# schematic.net
KiCad netlist of a schematic drawn in EAGLE
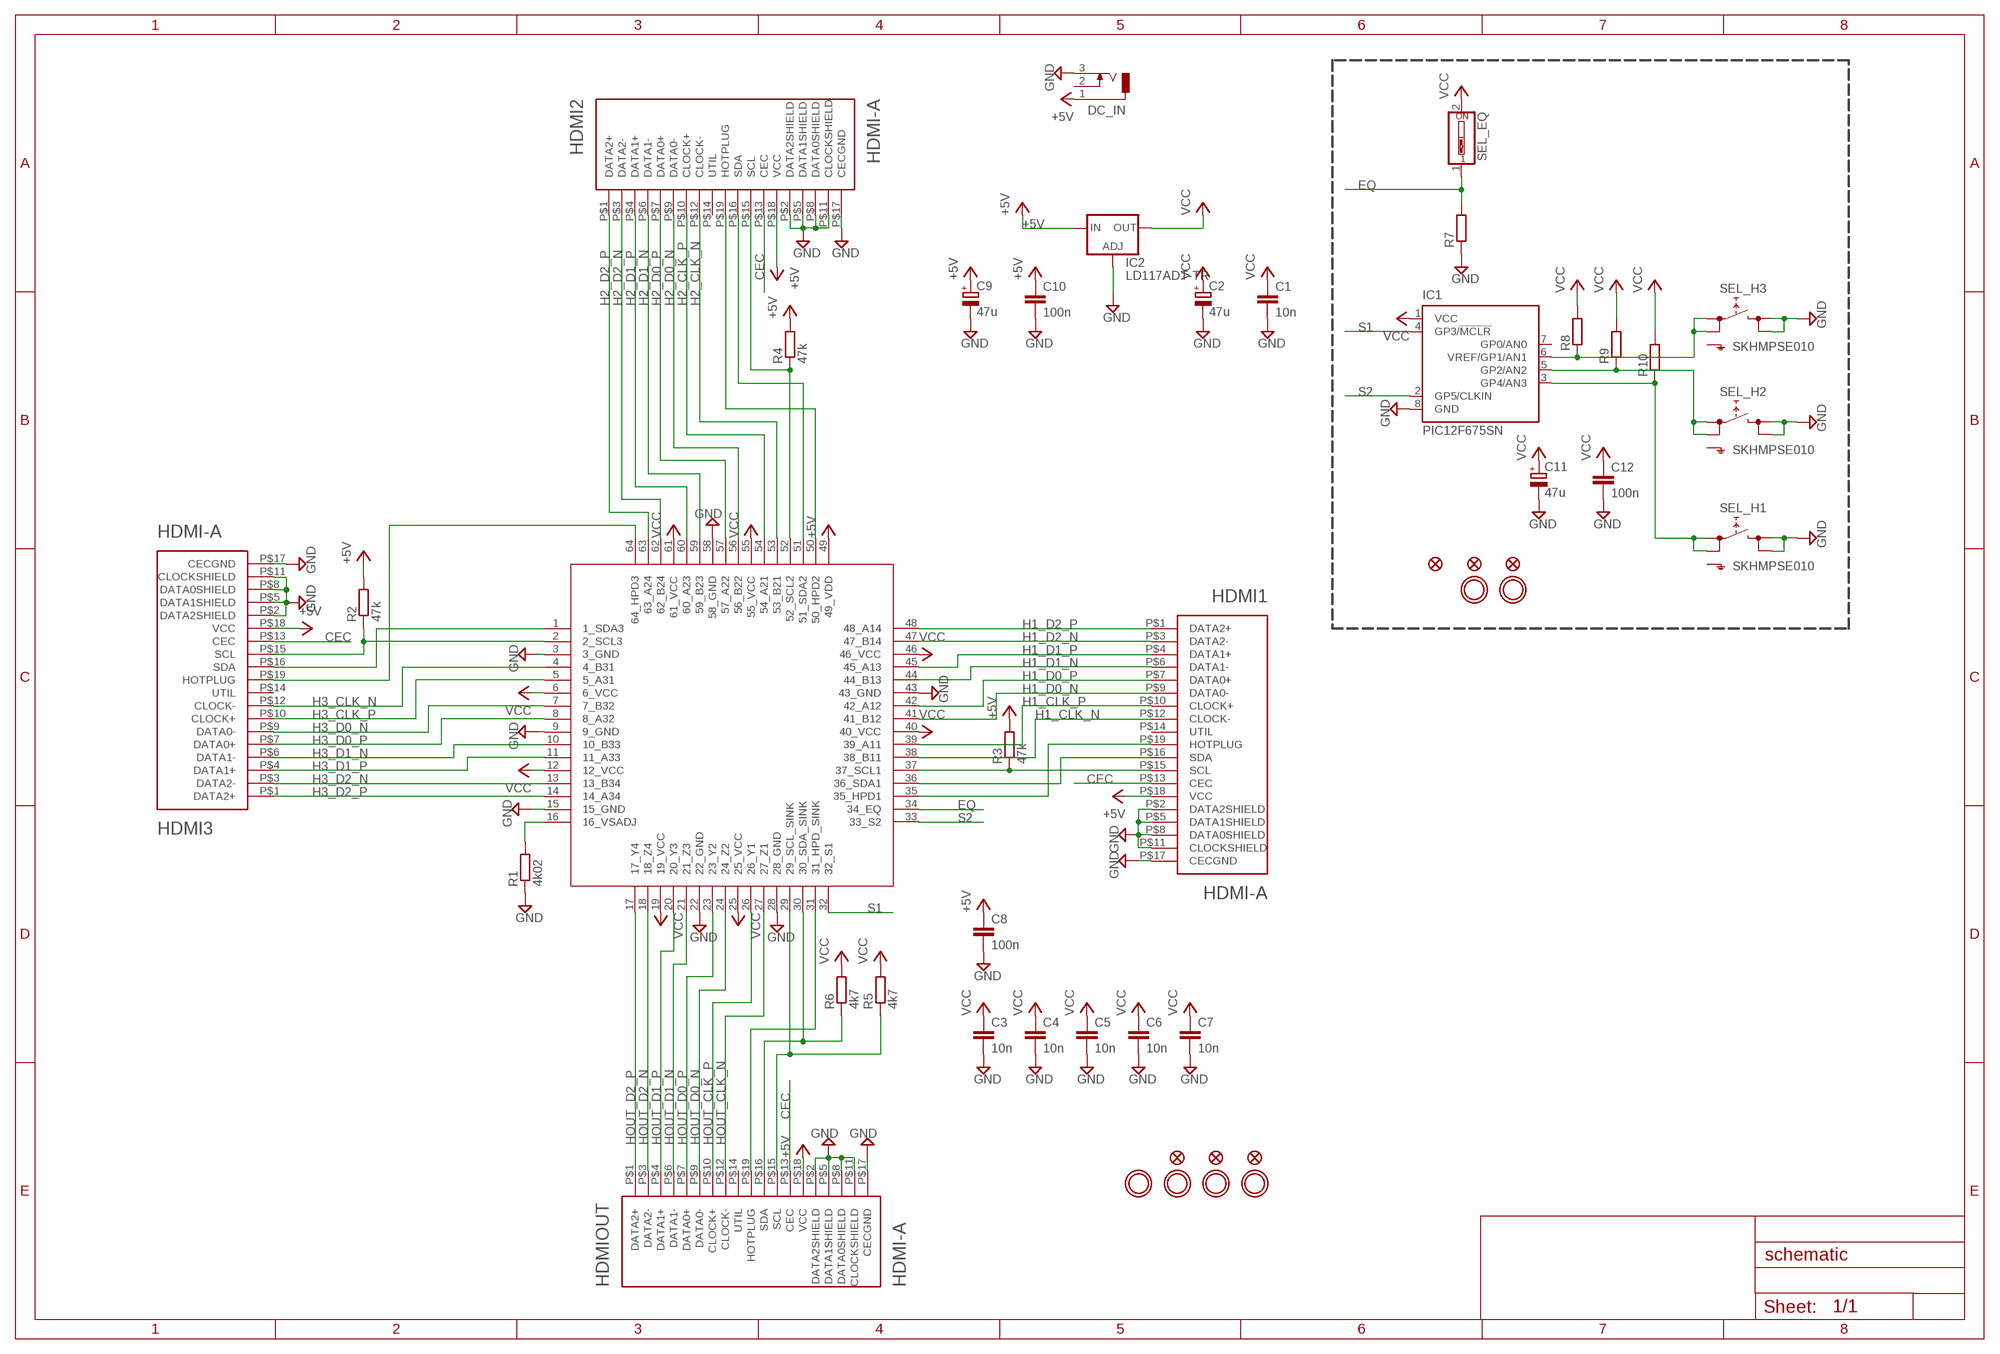
[diagram p0: schematic, sheet 1]

(export (version "E")
  (design (tool "Eeschema 10.0.6"))
  (components
    (comp (ref "C1")
      (value "10n")
      (footprint "eagle-import:C0402")
      (libsource (lib "eagle-import") (part "C-EUC0402"))
    )
    (comp (ref "C2")
      (value "47u")
      (footprint "eagle-import:SMC_A")
      (libsource (lib "eagle-import") (part "CPOL-EUSMCA"))
    )
    (comp (ref "C3")
      (value "10n")
      (footprint "eagle-import:0402")
      (libsource (lib "eagle-import") (part "C0402"))
    )
    (comp (ref "C4")
      (value "10n")
      (footprint "eagle-import:0402")
      (libsource (lib "eagle-import") (part "C0402"))
    )
    (comp (ref "C5")
      (value "10n")
      (footprint "eagle-import:0402")
      (libsource (lib "eagle-import") (part "C0402"))
    )
    (comp (ref "C6")
      (value "10n")
      (footprint "eagle-import:0402")
      (libsource (lib "eagle-import") (part "C0402"))
    )
    (comp (ref "C7")
      (value "10n")
      (footprint "eagle-import:0402")
      (libsource (lib "eagle-import") (part "C0402"))
    )
    (comp (ref "C8")
      (value "100n")
      (footprint "eagle-import:0402")
      (libsource (lib "eagle-import") (part "C0402"))
    )
    (comp (ref "C9")
      (value "47u")
      (footprint "eagle-import:SMC_A")
      (libsource (lib "eagle-import") (part "CPOL-EUSMCA"))
    )
    (comp (ref "C10")
      (value "100n")
      (footprint "eagle-import:C0402")
      (libsource (lib "eagle-import") (part "C-EUC0402"))
    )
    (comp (ref "C11")
      (value "47u")
      (footprint "eagle-import:SMC_A")
      (libsource (lib "eagle-import") (part "CPOL-EUSMCA"))
    )
    (comp (ref "C12")
      (value "100n")
      (footprint "eagle-import:C0402")
      (libsource (lib "eagle-import") (part "C-EUC0402"))
    )
    (comp (ref "DC_IN")
      (value "DCJ0303")
      (footprint "eagle-import:DCJ0303")
      (libsource (lib "eagle-import") (part "DCJ0303"))
    )
    (comp (ref "FID1")
      (value "FIDUCIAL\"\"")
      (footprint "eagle-import:FIDUCIAL_1MM")
      (libsource (lib "eagle-import") (part "FIDUCIAL{dblquote}{dblquote}"))
    )
    (comp (ref "FID2")
      (value "FIDUCIAL\"\"")
      (footprint "eagle-import:FIDUCIAL_1MM")
      (libsource (lib "eagle-import") (part "FIDUCIAL{dblquote}{dblquote}"))
    )
    (comp (ref "FID3")
      (value "FIDUCIAL\"\"")
      (footprint "eagle-import:FIDUCIAL_1MM")
      (libsource (lib "eagle-import") (part "FIDUCIAL{dblquote}{dblquote}"))
    )
    (comp (ref "FID4")
      (value "FIDUCIAL\"\"")
      (footprint "eagle-import:FIDUCIAL_1MM")
      (libsource (lib "eagle-import") (part "FIDUCIAL{dblquote}{dblquote}"))
    )
    (comp (ref "FID5")
      (value "FIDUCIAL\"\"")
      (footprint "eagle-import:FIDUCIAL_1MM")
      (libsource (lib "eagle-import") (part "FIDUCIAL{dblquote}{dblquote}"))
    )
    (comp (ref "FID6")
      (value "FIDUCIAL\"\"")
      (footprint "eagle-import:FIDUCIAL_1MM")
      (libsource (lib "eagle-import") (part "FIDUCIAL{dblquote}{dblquote}"))
    )
    (comp (ref "HDMI1")
      (value "HDMI-A")
      (footprint "eagle-import:HDMI_A")
      (libsource (lib "eagle-import") (part "HDMI-A"))
    )
    (comp (ref "HDMI2")
      (value "HDMI-A")
      (footprint "eagle-import:HDMI_A")
      (libsource (lib "eagle-import") (part "HDMI-A"))
    )
    (comp (ref "HDMI3")
      (value "HDMI-A")
      (footprint "eagle-import:HDMI_A")
      (libsource (lib "eagle-import") (part "HDMI-A"))
    )
    (comp (ref "HDMIOUT")
      (value "HDMI-A")
      (footprint "eagle-import:HDMI_A")
      (libsource (lib "eagle-import") (part "HDMI-A"))
    )
    (comp (ref "IC1")
      (value "PIC12F675SN")
      (footprint "eagle-import:SO-08")
      (fields (field (name "MF") "MICROCHIP") (field (name "MPN") "PIC12F675-E/SN"))
      (libsource (lib "eagle-import") (part "PIC12F675SN"))
    )
    (comp (ref "IC2")
      (value "LD117ADT-TR")
      (footprint "eagle-import:DPACK")
      (libsource (lib "eagle-import") (part "LD117A?DT-TR"))
    )
    (comp (ref "R1")
      (value "4k02")
      (footprint "eagle-import:0402")
      (libsource (lib "eagle-import") (part "R0402"))
    )
    (comp (ref "R2")
      (value "47k")
      (footprint "eagle-import:0402")
      (libsource (lib "eagle-import") (part "R0402"))
    )
    (comp (ref "R3")
      (value "47k")
      (footprint "eagle-import:0402")
      (libsource (lib "eagle-import") (part "R0402"))
    )
    (comp (ref "R4")
      (value "47k")
      (footprint "eagle-import:0402")
      (libsource (lib "eagle-import") (part "R0402"))
    )
    (comp (ref "R5")
      (value "4k7")
      (footprint "eagle-import:0402")
      (libsource (lib "eagle-import") (part "R0402"))
    )
    (comp (ref "R6")
      (value "4k7")
      (footprint "eagle-import:0402")
      (libsource (lib "eagle-import") (part "R0402"))
    )
    (comp (ref "R7")
      (value "R-EU_R0805")
      (footprint "eagle-import:R0805")
      (libsource (lib "eagle-import") (part "R-EU_R0805"))
    )
    (comp (ref "R8")
      (value "R-EU_R0805")
      (footprint "eagle-import:R0805")
      (libsource (lib "eagle-import") (part "R-EU_R0805"))
    )
    (comp (ref "R9")
      (value "R-EU_R0805")
      (footprint "eagle-import:R0805")
      (libsource (lib "eagle-import") (part "R-EU_R0805"))
    )
    (comp (ref "R10")
      (value "R-EU_R0805")
      (footprint "eagle-import:R0805")
      (libsource (lib "eagle-import") (part "R-EU_R0805"))
    )
    (comp (ref "SEL_EQ")
      (value "SW_DIP-1")
      (footprint "eagle-import:EDG-01")
      (libsource (lib "eagle-import") (part "SW_DIP-1"))
    )
    (comp (ref "SEL_H1")
      (value "SKHMPSE010")
      (footprint "eagle-import:SKHMPXE010")
      (libsource (lib "eagle-import") (part "SKHMPE010S"))
    )
    (comp (ref "SEL_H2")
      (value "SKHMPSE010")
      (footprint "eagle-import:SKHMPXE010")
      (libsource (lib "eagle-import") (part "SKHMPE010S"))
    )
    (comp (ref "SEL_H3")
      (value "SKHMPSE010")
      (footprint "eagle-import:SKHMPXE010")
      (libsource (lib "eagle-import") (part "SKHMPE010S"))
    )
    (comp (ref "U$1")
      (value "MOUNTINGHOLE3.0")
      (footprint "eagle-import:MOUNTINGHOLE_3.0_PLATED")
      (libsource (lib "eagle-import") (part "MOUNTINGHOLE3.0"))
    )
    (comp (ref "U$2")
      (value "MOUNTINGHOLE3.0")
      (footprint "eagle-import:MOUNTINGHOLE_3.0_PLATED")
      (libsource (lib "eagle-import") (part "MOUNTINGHOLE3.0"))
    )
    (comp (ref "U$31")
      (value "MOUNTINGHOLE3.0")
      (footprint "eagle-import:MOUNTINGHOLE_3.0_PLATED")
      (libsource (lib "eagle-import") (part "MOUNTINGHOLE3.0"))
    )
    (comp (ref "U$32")
      (value "MOUNTINGHOLE3.0")
      (footprint "eagle-import:MOUNTINGHOLE_3.0_PLATED")
      (libsource (lib "eagle-import") (part "MOUNTINGHOLE3.0"))
    )
    (comp (ref "U$33")
      (value "MOUNTINGHOLE3.0")
      (footprint "eagle-import:MOUNTINGHOLE_3.0_PLATED")
      (libsource (lib "eagle-import") (part "MOUNTINGHOLE3.0"))
    )
    (comp (ref "U$34")
      (value "MOUNTINGHOLE3.0")
      (footprint "eagle-import:MOUNTINGHOLE_3.0_PLATED")
      (libsource (lib "eagle-import") (part "MOUNTINGHOLE3.0"))
    )
    (comp (ref "U1")
      (value "TMDS351TQFP64")
      (footprint "eagle-import:QFP50P1200X1200X120-64")
      (libsource (lib "eagle-import") (part "TMDS351TQFP64"))
    )
  )
  (nets
    (net (code "1") (name "+5V") (class "Default")
      (node (ref "C10") (pin "1") (pinfunction "1_1") (pintype "passive"))
      (node (ref "C8") (pin "1") (pinfunction "1_1") (pintype "passive"))
      (node (ref "C9") (pin "+") (pinfunction "+_+") (pintype "passive"))
      (node (ref "DC_IN") (pin "1") (pinfunction "1_1") (pintype "passive"))
      (node (ref "HDMI1") (pin "P$18") (pinfunction "VCC_P$18") (pintype "bidirectional"))
      (node (ref "HDMI2") (pin "P$18") (pinfunction "VCC_P$18") (pintype "bidirectional"))
      (node (ref "HDMI3") (pin "P$18") (pinfunction "VCC_P$18") (pintype "bidirectional"))
      (node (ref "HDMIOUT") (pin "P$18") (pinfunction "VCC_P$18") (pintype "bidirectional"))
      (node (ref "IC2") (pin "3") (pinfunction "IN_3") (pintype "input"))
      (node (ref "R2") (pin "2") (pinfunction "2_2") (pintype "passive"))
      (node (ref "R3") (pin "2") (pinfunction "2_2") (pintype "passive"))
      (node (ref "R4") (pin "2") (pinfunction "2_2") (pintype "passive"))
      (node (ref "U1") (pin "49") (pinfunction "49_VDD_49") (pintype "bidirectional"))
    )
    (net (code "2") (name "/CEC") (class "Default")
      (node (ref "HDMI1") (pin "P$13") (pinfunction "CEC_P$13") (pintype "bidirectional"))
      (node (ref "HDMI2") (pin "P$13") (pinfunction "CEC_P$13") (pintype "bidirectional"))
      (node (ref "HDMI3") (pin "P$13") (pinfunction "CEC_P$13") (pintype "bidirectional"))
      (node (ref "HDMIOUT") (pin "P$13") (pinfunction "CEC_P$13") (pintype "bidirectional"))
    )
    (net (code "3") (name "/EQ") (class "Default")
      (node (ref "R7") (pin "2") (pinfunction "2_2") (pintype "passive"))
      (node (ref "SEL_EQ") (pin "1") (pinfunction "1_1") (pintype "passive"))
      (node (ref "U1") (pin "34") (pinfunction "34_EQ_34") (pintype "bidirectional"))
    )
    (net (code "4") (name "/H1_CLK_N") (class "Default")
      (node (ref "HDMI1") (pin "P$12") (pinfunction "CLOCK-_P$12") (pintype "bidirectional"))
      (node (ref "U1") (pin "38") (pinfunction "38_B11_38") (pintype "bidirectional"))
    )
    (net (code "5") (name "/H1_CLK_P") (class "Default")
      (node (ref "HDMI1") (pin "P$10") (pinfunction "CLOCK+_P$10") (pintype "bidirectional"))
      (node (ref "U1") (pin "39") (pinfunction "39_A11_39") (pintype "bidirectional"))
    )
    (net (code "6") (name "/H1_D0_N") (class "Default")
      (node (ref "HDMI1") (pin "P$9") (pinfunction "DATA0-_P$9") (pintype "bidirectional"))
      (node (ref "U1") (pin "41") (pinfunction "41_B12_41") (pintype "bidirectional"))
    )
    (net (code "7") (name "/H1_D0_P") (class "Default")
      (node (ref "HDMI1") (pin "P$7") (pinfunction "DATA0+_P$7") (pintype "bidirectional"))
      (node (ref "U1") (pin "42") (pinfunction "42_A12_42") (pintype "bidirectional"))
    )
    (net (code "8") (name "/H1_D1_N") (class "Default")
      (node (ref "HDMI1") (pin "P$6") (pinfunction "DATA1-_P$6") (pintype "bidirectional"))
      (node (ref "U1") (pin "44") (pinfunction "44_B13_44") (pintype "bidirectional"))
    )
    (net (code "9") (name "/H1_D1_P") (class "Default")
      (node (ref "HDMI1") (pin "P$4") (pinfunction "DATA1+_P$4") (pintype "bidirectional"))
      (node (ref "U1") (pin "45") (pinfunction "45_A13_45") (pintype "bidirectional"))
    )
    (net (code "10") (name "/H1_D2_N") (class "Default")
      (node (ref "HDMI1") (pin "P$3") (pinfunction "DATA2-_P$3") (pintype "bidirectional"))
      (node (ref "U1") (pin "47") (pinfunction "47_B14_47") (pintype "bidirectional"))
    )
    (net (code "11") (name "/H1_D2_P") (class "Default")
      (node (ref "HDMI1") (pin "P$1") (pinfunction "DATA2+_P$1") (pintype "bidirectional"))
      (node (ref "U1") (pin "48") (pinfunction "48_A14_48") (pintype "bidirectional"))
    )
    (net (code "12") (name "/H2_CLK_N") (class "Default")
      (node (ref "HDMI2") (pin "P$12") (pinfunction "CLOCK-_P$12") (pintype "bidirectional"))
      (node (ref "U1") (pin "53") (pinfunction "53_B21_53") (pintype "bidirectional"))
    )
    (net (code "13") (name "/H2_CLK_P") (class "Default")
      (node (ref "HDMI2") (pin "P$10") (pinfunction "CLOCK+_P$10") (pintype "bidirectional"))
      (node (ref "U1") (pin "54") (pinfunction "54_A21_54") (pintype "bidirectional"))
    )
    (net (code "14") (name "/H2_D0_N") (class "Default")
      (node (ref "HDMI2") (pin "P$9") (pinfunction "DATA0-_P$9") (pintype "bidirectional"))
      (node (ref "U1") (pin "56") (pinfunction "56_B22_56") (pintype "bidirectional"))
    )
    (net (code "15") (name "/H2_D0_P") (class "Default")
      (node (ref "HDMI2") (pin "P$7") (pinfunction "DATA0+_P$7") (pintype "bidirectional"))
      (node (ref "U1") (pin "57") (pinfunction "57_A22_57") (pintype "bidirectional"))
    )
    (net (code "16") (name "/H2_D1_N") (class "Default")
      (node (ref "HDMI2") (pin "P$6") (pinfunction "DATA1-_P$6") (pintype "bidirectional"))
      (node (ref "U1") (pin "59") (pinfunction "59_B23_59") (pintype "bidirectional"))
    )
    (net (code "17") (name "/H2_D1_P") (class "Default")
      (node (ref "HDMI2") (pin "P$4") (pinfunction "DATA1+_P$4") (pintype "bidirectional"))
      (node (ref "U1") (pin "60") (pinfunction "60_A23_60") (pintype "bidirectional"))
    )
    (net (code "18") (name "/H2_D2_N") (class "Default")
      (node (ref "HDMI2") (pin "P$3") (pinfunction "DATA2-_P$3") (pintype "bidirectional"))
      (node (ref "U1") (pin "62") (pinfunction "62_B24_62") (pintype "bidirectional"))
    )
    (net (code "19") (name "/H2_D2_P") (class "Default")
      (node (ref "HDMI2") (pin "P$1") (pinfunction "DATA2+_P$1") (pintype "bidirectional"))
      (node (ref "U1") (pin "63") (pinfunction "63_A24_63") (pintype "bidirectional"))
    )
    (net (code "20") (name "/H3_CLK_N") (class "Default")
      (node (ref "HDMI3") (pin "P$12") (pinfunction "CLOCK-_P$12") (pintype "bidirectional"))
      (node (ref "U1") (pin "4") (pinfunction "4_B31_4") (pintype "bidirectional"))
    )
    (net (code "21") (name "/H3_CLK_P") (class "Default")
      (node (ref "HDMI3") (pin "P$10") (pinfunction "CLOCK+_P$10") (pintype "bidirectional"))
      (node (ref "U1") (pin "5") (pinfunction "5_A31_5") (pintype "bidirectional"))
    )
    (net (code "22") (name "/H3_D0_N") (class "Default")
      (node (ref "HDMI3") (pin "P$9") (pinfunction "DATA0-_P$9") (pintype "bidirectional"))
      (node (ref "U1") (pin "7") (pinfunction "7_B32_7") (pintype "bidirectional"))
    )
    (net (code "23") (name "/H3_D0_P") (class "Default")
      (node (ref "HDMI3") (pin "P$7") (pinfunction "DATA0+_P$7") (pintype "bidirectional"))
      (node (ref "U1") (pin "8") (pinfunction "8_A32_8") (pintype "bidirectional"))
    )
    (net (code "24") (name "/H3_D1_N") (class "Default")
      (node (ref "HDMI3") (pin "P$6") (pinfunction "DATA1-_P$6") (pintype "bidirectional"))
      (node (ref "U1") (pin "10") (pinfunction "10_B33_10") (pintype "bidirectional"))
    )
    (net (code "25") (name "/H3_D1_P") (class "Default")
      (node (ref "HDMI3") (pin "P$4") (pinfunction "DATA1+_P$4") (pintype "bidirectional"))
      (node (ref "U1") (pin "11") (pinfunction "11_A33_11") (pintype "bidirectional"))
    )
    (net (code "26") (name "/H3_D2_N") (class "Default")
      (node (ref "HDMI3") (pin "P$3") (pinfunction "DATA2-_P$3") (pintype "bidirectional"))
      (node (ref "U1") (pin "13") (pinfunction "13_B34_13") (pintype "bidirectional"))
    )
    (net (code "27") (name "/H3_D2_P") (class "Default")
      (node (ref "HDMI3") (pin "P$1") (pinfunction "DATA2+_P$1") (pintype "bidirectional"))
      (node (ref "U1") (pin "14") (pinfunction "14_A34_14") (pintype "bidirectional"))
    )
    (net (code "28") (name "/HOUT_CLK_N") (class "Default")
      (node (ref "HDMIOUT") (pin "P$12") (pinfunction "CLOCK-_P$12") (pintype "bidirectional"))
      (node (ref "U1") (pin "27") (pinfunction "27_Z1_27") (pintype "bidirectional"))
    )
    (net (code "29") (name "/HOUT_CLK_P") (class "Default")
      (node (ref "HDMIOUT") (pin "P$10") (pinfunction "CLOCK+_P$10") (pintype "bidirectional"))
      (node (ref "U1") (pin "26") (pinfunction "26_Y1_26") (pintype "bidirectional"))
    )
    (net (code "30") (name "/HOUT_D0_N") (class "Default")
      (node (ref "HDMIOUT") (pin "P$9") (pinfunction "DATA0-_P$9") (pintype "bidirectional"))
      (node (ref "U1") (pin "24") (pinfunction "24_Z2_24") (pintype "bidirectional"))
    )
    (net (code "31") (name "/HOUT_D0_P") (class "Default")
      (node (ref "HDMIOUT") (pin "P$7") (pinfunction "DATA0+_P$7") (pintype "bidirectional"))
      (node (ref "U1") (pin "23") (pinfunction "23_Y2_23") (pintype "bidirectional"))
    )
    (net (code "32") (name "/HOUT_D1_N") (class "Default")
      (node (ref "HDMIOUT") (pin "P$6") (pinfunction "DATA1-_P$6") (pintype "bidirectional"))
      (node (ref "U1") (pin "21") (pinfunction "21_Z3_21") (pintype "bidirectional"))
    )
    (net (code "33") (name "/HOUT_D1_P") (class "Default")
      (node (ref "HDMIOUT") (pin "P$4") (pinfunction "DATA1+_P$4") (pintype "bidirectional"))
      (node (ref "U1") (pin "20") (pinfunction "20_Y3_20") (pintype "bidirectional"))
    )
    (net (code "34") (name "/HOUT_D2_N") (class "Default")
      (node (ref "HDMIOUT") (pin "P$3") (pinfunction "DATA2-_P$3") (pintype "bidirectional"))
      (node (ref "U1") (pin "18") (pinfunction "18_Z4_18") (pintype "bidirectional"))
    )
    (net (code "35") (name "/HOUT_D2_P") (class "Default")
      (node (ref "HDMIOUT") (pin "P$1") (pinfunction "DATA2+_P$1") (pintype "bidirectional"))
      (node (ref "U1") (pin "17") (pinfunction "17_Y4_17") (pintype "bidirectional"))
    )
    (net (code "36") (name "/S1") (class "Default")
      (node (ref "IC1") (pin "4") (pinfunction "GP3/~{MCLR}_4") (pintype "input"))
      (node (ref "U1") (pin "32") (pinfunction "32_S1_32") (pintype "bidirectional"))
    )
    (net (code "37") (name "/S2") (class "Default")
      (node (ref "IC1") (pin "2") (pinfunction "GP5/CLKIN_2") (pintype "bidirectional"))
      (node (ref "U1") (pin "33") (pinfunction "33_S2_33") (pintype "bidirectional"))
    )
    (net (code "38") (name "GND") (class "Default")
      (node (ref "C1") (pin "2") (pinfunction "2_2") (pintype "passive"))
      (node (ref "C10") (pin "2") (pinfunction "2_2") (pintype "passive"))
      (node (ref "C11") (pin "-") (pinfunction "-_-") (pintype "passive"))
      (node (ref "C12") (pin "2") (pinfunction "2_2") (pintype "passive"))
      (node (ref "C2") (pin "-") (pinfunction "-_-") (pintype "passive"))
      (node (ref "C3") (pin "2") (pinfunction "2_2") (pintype "passive"))
      (node (ref "C4") (pin "2") (pinfunction "2_2") (pintype "passive"))
      (node (ref "C5") (pin "2") (pinfunction "2_2") (pintype "passive"))
      (node (ref "C6") (pin "2") (pinfunction "2_2") (pintype "passive"))
      (node (ref "C7") (pin "2") (pinfunction "2_2") (pintype "passive"))
      (node (ref "C8") (pin "2") (pinfunction "2_2") (pintype "passive"))
      (node (ref "C9") (pin "-") (pinfunction "-_-") (pintype "passive"))
      (node (ref "DC_IN") (pin "3") (pinfunction "3_3") (pintype "passive"))
      (node (ref "HDMI1") (pin "P$11") (pinfunction "CLOCKSHIELD_P$11") (pintype "bidirectional"))
      (node (ref "HDMI1") (pin "P$17") (pinfunction "CECGND_P$17") (pintype "bidirectional"))
      (node (ref "HDMI1") (pin "P$2") (pinfunction "DATA2SHIELD_P$2") (pintype "bidirectional"))
      (node (ref "HDMI1") (pin "P$5") (pinfunction "DATA1SHIELD_P$5") (pintype "bidirectional"))
      (node (ref "HDMI1") (pin "P$8") (pinfunction "DATA0SHIELD_P$8") (pintype "bidirectional"))
      (node (ref "HDMI2") (pin "P$11") (pinfunction "CLOCKSHIELD_P$11") (pintype "bidirectional"))
      (node (ref "HDMI2") (pin "P$17") (pinfunction "CECGND_P$17") (pintype "bidirectional"))
      (node (ref "HDMI2") (pin "P$2") (pinfunction "DATA2SHIELD_P$2") (pintype "bidirectional"))
      (node (ref "HDMI2") (pin "P$5") (pinfunction "DATA1SHIELD_P$5") (pintype "bidirectional"))
      (node (ref "HDMI2") (pin "P$8") (pinfunction "DATA0SHIELD_P$8") (pintype "bidirectional"))
      (node (ref "HDMI3") (pin "P$11") (pinfunction "CLOCKSHIELD_P$11") (pintype "bidirectional"))
      (node (ref "HDMI3") (pin "P$17") (pinfunction "CECGND_P$17") (pintype "bidirectional"))
      (node (ref "HDMI3") (pin "P$2") (pinfunction "DATA2SHIELD_P$2") (pintype "bidirectional"))
      (node (ref "HDMI3") (pin "P$5") (pinfunction "DATA1SHIELD_P$5") (pintype "bidirectional"))
      (node (ref "HDMI3") (pin "P$8") (pinfunction "DATA0SHIELD_P$8") (pintype "bidirectional"))
      (node (ref "HDMIOUT") (pin "P$11") (pinfunction "CLOCKSHIELD_P$11") (pintype "bidirectional"))
      (node (ref "HDMIOUT") (pin "P$17") (pinfunction "CECGND_P$17") (pintype "bidirectional"))
      (node (ref "HDMIOUT") (pin "P$2") (pinfunction "DATA2SHIELD_P$2") (pintype "bidirectional"))
      (node (ref "HDMIOUT") (pin "P$5") (pinfunction "DATA1SHIELD_P$5") (pintype "bidirectional"))
      (node (ref "HDMIOUT") (pin "P$8") (pinfunction "DATA0SHIELD_P$8") (pintype "bidirectional"))
      (node (ref "IC1") (pin "8") (pinfunction "GND_8") (pintype "power_in"))
      (node (ref "IC2") (pin "1") (pinfunction "ADJ_1") (pintype "input"))
      (node (ref "R1") (pin "1") (pinfunction "1_1") (pintype "passive"))
      (node (ref "R7") (pin "1") (pinfunction "1_1") (pintype "passive"))
      (node (ref "SEL_H1") (pin "3") (pinfunction "2.1_3") (pintype "passive"))
      (node (ref "SEL_H1") (pin "4") (pinfunction "2.2_4") (pintype "passive"))
      (node (ref "SEL_H2") (pin "3") (pinfunction "2.1_3") (pintype "passive"))
      (node (ref "SEL_H2") (pin "4") (pinfunction "2.2_4") (pintype "passive"))
      (node (ref "SEL_H3") (pin "3") (pinfunction "2.1_3") (pintype "passive"))
      (node (ref "SEL_H3") (pin "4") (pinfunction "2.2_4") (pintype "passive"))
      (node (ref "U1") (pin "15") (pinfunction "15_GND_15") (pintype "bidirectional"))
      (node (ref "U1") (pin "22") (pinfunction "22_GND_22") (pintype "bidirectional"))
      (node (ref "U1") (pin "28") (pinfunction "28_GND_28") (pintype "bidirectional"))
      (node (ref "U1") (pin "3") (pinfunction "3_GND_3") (pintype "bidirectional"))
      (node (ref "U1") (pin "43") (pinfunction "43_GND_43") (pintype "bidirectional"))
      (node (ref "U1") (pin "58") (pinfunction "58_GND_58") (pintype "bidirectional"))
      (node (ref "U1") (pin "9") (pinfunction "9_GND_9") (pintype "bidirectional"))
    )
    (net (code "39") (name "Net-(HDMI1-HOTPLUG)") (class "Default")
      (node (ref "HDMI1") (pin "P$19") (pinfunction "HOTPLUG_P$19") (pintype "bidirectional"))
      (node (ref "U1") (pin "35") (pinfunction "35_HPD1_35") (pintype "bidirectional"))
    )
    (net (code "40") (name "Net-(HDMI1-SCL)") (class "Default")
      (node (ref "HDMI1") (pin "P$15") (pinfunction "SCL_P$15") (pintype "bidirectional"))
      (node (ref "R3") (pin "1") (pinfunction "1_1") (pintype "passive"))
      (node (ref "U1") (pin "37") (pinfunction "37_SCL1_37") (pintype "bidirectional"))
    )
    (net (code "41") (name "Net-(HDMI1-SDA)") (class "Default")
      (node (ref "HDMI1") (pin "P$16") (pinfunction "SDA_P$16") (pintype "bidirectional"))
      (node (ref "U1") (pin "36") (pinfunction "36_SDA1_36") (pintype "bidirectional"))
    )
    (net (code "42") (name "Net-(HDMI2-HOTPLUG)") (class "Default")
      (node (ref "HDMI2") (pin "P$19") (pinfunction "HOTPLUG_P$19") (pintype "bidirectional"))
      (node (ref "U1") (pin "50") (pinfunction "50_HPD2_50") (pintype "bidirectional"))
    )
    (net (code "43") (name "Net-(HDMI2-SCL)") (class "Default")
      (node (ref "HDMI2") (pin "P$15") (pinfunction "SCL_P$15") (pintype "bidirectional"))
      (node (ref "R4") (pin "1") (pinfunction "1_1") (pintype "passive"))
      (node (ref "U1") (pin "52") (pinfunction "52_SCL2_52") (pintype "bidirectional"))
    )
    (net (code "44") (name "Net-(HDMI2-SDA)") (class "Default")
      (node (ref "HDMI2") (pin "P$16") (pinfunction "SDA_P$16") (pintype "bidirectional"))
      (node (ref "U1") (pin "51") (pinfunction "51_SDA2_51") (pintype "bidirectional"))
    )
    (net (code "45") (name "Net-(HDMI3-HOTPLUG)") (class "Default")
      (node (ref "HDMI3") (pin "P$19") (pinfunction "HOTPLUG_P$19") (pintype "bidirectional"))
      (node (ref "U1") (pin "64") (pinfunction "64_HPD3_64") (pintype "bidirectional"))
    )
    (net (code "46") (name "Net-(HDMI3-SCL)") (class "Default")
      (node (ref "HDMI3") (pin "P$15") (pinfunction "SCL_P$15") (pintype "bidirectional"))
      (node (ref "R2") (pin "1") (pinfunction "1_1") (pintype "passive"))
      (node (ref "U1") (pin "2") (pinfunction "2_SCL3_2") (pintype "bidirectional"))
    )
    (net (code "47") (name "Net-(HDMI3-SDA)") (class "Default")
      (node (ref "HDMI3") (pin "P$16") (pinfunction "SDA_P$16") (pintype "bidirectional"))
      (node (ref "U1") (pin "1") (pinfunction "1_SDA3_1") (pintype "bidirectional"))
    )
    (net (code "48") (name "Net-(HDMIOUT-HOTPLUG)") (class "Default")
      (node (ref "HDMIOUT") (pin "P$19") (pinfunction "HOTPLUG_P$19") (pintype "bidirectional"))
      (node (ref "U1") (pin "31") (pinfunction "31_HPD_SINK_31") (pintype "bidirectional"))
    )
    (net (code "49") (name "Net-(HDMIOUT-SCL)") (class "Default")
      (node (ref "HDMIOUT") (pin "P$15") (pinfunction "SCL_P$15") (pintype "bidirectional"))
      (node (ref "R5") (pin "1") (pinfunction "1_1") (pintype "passive"))
      (node (ref "U1") (pin "29") (pinfunction "29_SCL_SINK_29") (pintype "bidirectional"))
    )
    (net (code "50") (name "Net-(HDMIOUT-SDA)") (class "Default")
      (node (ref "HDMIOUT") (pin "P$16") (pinfunction "SDA_P$16") (pintype "bidirectional"))
      (node (ref "R6") (pin "1") (pinfunction "1_1") (pintype "passive"))
      (node (ref "U1") (pin "30") (pinfunction "30_SDA_SINK_30") (pintype "bidirectional"))
    )
    (net (code "51") (name "Net-(IC1-GP2{slash}AN2)") (class "Default")
      (node (ref "IC1") (pin "5") (pinfunction "GP2/AN2_5") (pintype "bidirectional"))
      (node (ref "R9") (pin "1") (pinfunction "1_1") (pintype "passive"))
      (node (ref "SEL_H2") (pin "1") (pinfunction "1.1_1") (pintype "passive"))
      (node (ref "SEL_H2") (pin "2") (pinfunction "1.2_2") (pintype "passive"))
    )
    (net (code "52") (name "Net-(IC1-GP4{slash}AN3)") (class "Default")
      (node (ref "IC1") (pin "3") (pinfunction "GP4/AN3_3") (pintype "bidirectional"))
      (node (ref "R10") (pin "1") (pinfunction "1_1") (pintype "passive"))
      (node (ref "SEL_H1") (pin "1") (pinfunction "1.1_1") (pintype "passive"))
      (node (ref "SEL_H1") (pin "2") (pinfunction "1.2_2") (pintype "passive"))
    )
    (net (code "53") (name "Net-(IC1-VREF{slash}GP1{slash}AN1)") (class "Default")
      (node (ref "IC1") (pin "6") (pinfunction "VREF/GP1/AN1_6") (pintype "bidirectional"))
      (node (ref "R8") (pin "1") (pinfunction "1_1") (pintype "passive"))
      (node (ref "SEL_H3") (pin "1") (pinfunction "1.1_1") (pintype "passive"))
      (node (ref "SEL_H3") (pin "2") (pinfunction "1.2_2") (pintype "passive"))
    )
    (net (code "54") (name "Net-(U1-16_VSADJ)") (class "Default")
      (node (ref "R1") (pin "2") (pinfunction "2_2") (pintype "passive"))
      (node (ref "U1") (pin "16") (pinfunction "16_VSADJ_16") (pintype "bidirectional"))
    )
    (net (code "55") (name "VCC") (class "Default")
      (node (ref "C1") (pin "1") (pinfunction "1_1") (pintype "passive"))
      (node (ref "C11") (pin "+") (pinfunction "+_+") (pintype "passive"))
      (node (ref "C12") (pin "1") (pinfunction "1_1") (pintype "passive"))
      (node (ref "C2") (pin "+") (pinfunction "+_+") (pintype "passive"))
      (node (ref "C3") (pin "1") (pinfunction "1_1") (pintype "passive"))
      (node (ref "C4") (pin "1") (pinfunction "1_1") (pintype "passive"))
      (node (ref "C5") (pin "1") (pinfunction "1_1") (pintype "passive"))
      (node (ref "C6") (pin "1") (pinfunction "1_1") (pintype "passive"))
      (node (ref "C7") (pin "1") (pinfunction "1_1") (pintype "passive"))
      (node (ref "IC1") (pin "1") (pinfunction "VCC_1") (pintype "power_in"))
      (node (ref "IC2") (pin "4") (pinfunction "OUT_4") (pintype "passive"))
      (node (ref "R10") (pin "2") (pinfunction "2_2") (pintype "passive"))
      (node (ref "R5") (pin "2") (pinfunction "2_2") (pintype "passive"))
      (node (ref "R6") (pin "2") (pinfunction "2_2") (pintype "passive"))
      (node (ref "R8") (pin "2") (pinfunction "2_2") (pintype "passive"))
      (node (ref "R9") (pin "2") (pinfunction "2_2") (pintype "passive"))
      (node (ref "SEL_EQ") (pin "2") (pinfunction "2_2") (pintype "passive"))
      (node (ref "U1") (pin "12") (pinfunction "12_VCC_12") (pintype "bidirectional"))
      (node (ref "U1") (pin "19") (pinfunction "19_VCC_19") (pintype "bidirectional"))
      (node (ref "U1") (pin "25") (pinfunction "25_VCC_25") (pintype "bidirectional"))
      (node (ref "U1") (pin "40") (pinfunction "40_VCC_40") (pintype "bidirectional"))
      (node (ref "U1") (pin "46") (pinfunction "46_VCC_46") (pintype "bidirectional"))
      (node (ref "U1") (pin "55") (pinfunction "55_VCC_55") (pintype "bidirectional"))
      (node (ref "U1") (pin "6") (pinfunction "6_VCC_6") (pintype "bidirectional"))
      (node (ref "U1") (pin "61") (pinfunction "61_VCC_61") (pintype "bidirectional"))
    )
    (net (code "56") (name "unconnected-(DC_IN-Pad2)") (class "Default")
      (node (ref "DC_IN") (pin "2") (pinfunction "2_2") (pintype "passive"))
    )
    (net (code "57") (name "unconnected-(HDMI1-UTIL-PadP$14)") (class "Default")
      (node (ref "HDMI1") (pin "P$14") (pinfunction "UTIL_P$14") (pintype "bidirectional"))
    )
    (net (code "58") (name "unconnected-(HDMI2-UTIL-PadP$14)") (class "Default")
      (node (ref "HDMI2") (pin "P$14") (pinfunction "UTIL_P$14") (pintype "bidirectional"))
    )
    (net (code "59") (name "unconnected-(HDMI3-UTIL-PadP$14)") (class "Default")
      (node (ref "HDMI3") (pin "P$14") (pinfunction "UTIL_P$14") (pintype "bidirectional"))
    )
    (net (code "60") (name "unconnected-(HDMIOUT-UTIL-PadP$14)") (class "Default")
      (node (ref "HDMIOUT") (pin "P$14") (pinfunction "UTIL_P$14") (pintype "bidirectional"))
    )
    (net (code "61") (name "unconnected-(IC1-GP0{slash}AN0-Pad7)") (class "Default")
      (node (ref "IC1") (pin "7") (pinfunction "GP0/AN0_7") (pintype "bidirectional"))
    )
    (net (code "62") (name "unconnected-(SEL_H1-SH-Pad5)") (class "Default")
      (node (ref "SEL_H1") (pin "5") (pinfunction "SH_5") (pintype "passive"))
    )
    (net (code "63") (name "unconnected-(SEL_H2-SH-Pad5)") (class "Default")
      (node (ref "SEL_H2") (pin "5") (pinfunction "SH_5") (pintype "passive"))
    )
    (net (code "64") (name "unconnected-(SEL_H3-SH-Pad5)") (class "Default")
      (node (ref "SEL_H3") (pin "5") (pinfunction "SH_5") (pintype "passive"))
    )
  )
)
